# tdcs.net
KiCad netlist of a schematic drawn in EAGLE
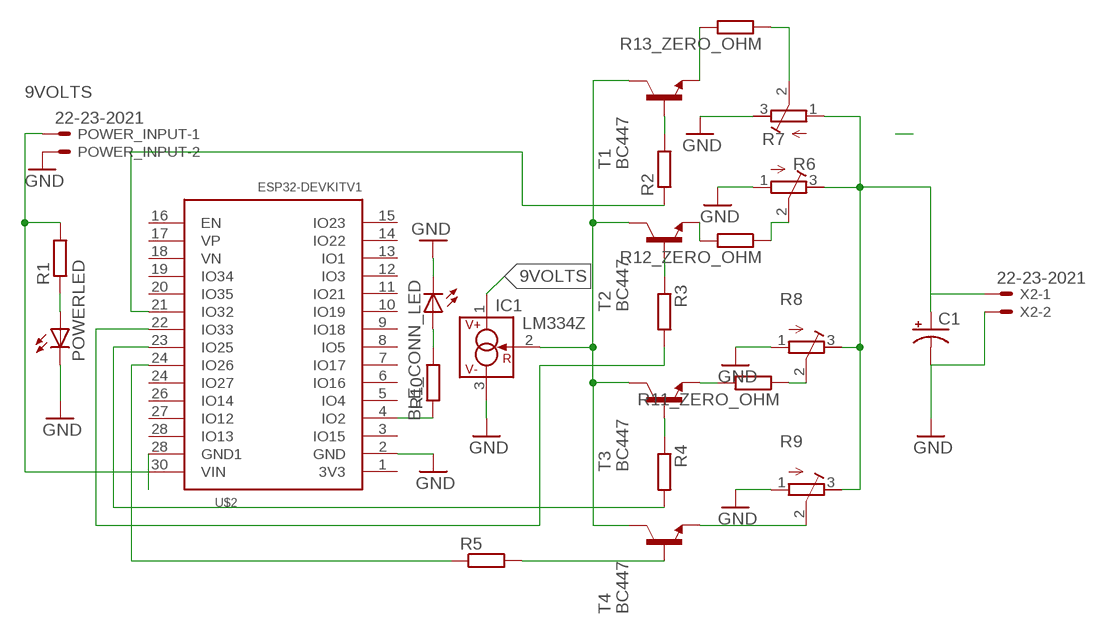
[diagram p0: schematic, sheet 1]

(export (version "E")
  (design (tool "Eeschema 10.0.6"))
  (components
    (comp (ref "BLE_CONN_LED")
      (value "LED3MM")
      (footprint "eagle-import:LED3MM")
      (libsource (lib "eagle-import") (part "LED3MM"))
    )
    (comp (ref "C1")
      (value "CPOL-USE1.8-4")
      (footprint "eagle-import:E1,8-4")
      (libsource (lib "eagle-import") (part "CPOL-USE1.8-4"))
    )
    (comp (ref "IC1")
      (value "LM334Z")
      (footprint "eagle-import:TO92")
      (libsource (lib "eagle-import") (part "LM34Z3"))
    )
    (comp (ref "POWERLED")
      (value "LEDB152")
      (footprint "eagle-import:Q62902-B152")
      (libsource (lib "eagle-import") (part "LEDB152"))
    )
    (comp (ref "POWER_INPUT")
      (value "22-23-2021")
      (footprint "eagle-import:22-23-2021")
      (fields (field (name "MF") "MOLEX"))
      (libsource (lib "eagle-import") (part "22-23-2021"))
    )
    (comp (ref "R1")
      (value "R-EU_0204/5")
      (footprint "eagle-import:0204_5")
      (libsource (lib "eagle-import") (part "R-EU_0204/5"))
    )
    (comp (ref "R2")
      (value "R-EU_0204/5")
      (footprint "eagle-import:0204_5")
      (libsource (lib "eagle-import") (part "R-EU_0204/5"))
    )
    (comp (ref "R3")
      (value "R-EU_0204/5")
      (footprint "eagle-import:0204_5")
      (libsource (lib "eagle-import") (part "R-EU_0204/5"))
    )
    (comp (ref "R4")
      (value "R-EU_0204/5")
      (footprint "eagle-import:0204_5")
      (libsource (lib "eagle-import") (part "R-EU_0204/5"))
    )
    (comp (ref "R5")
      (value "R-EU_0204/5")
      (footprint "eagle-import:0204_5")
      (libsource (lib "eagle-import") (part "R-EU_0204/5"))
    )
    (comp (ref "R6")
      (value "R-TRIMM64W")
      (footprint "eagle-import:RTRIM64W")
      (libsource (lib "eagle-import") (part "R-TRIMM64W"))
    )
    (comp (ref "R7")
      (value "R-TRIMM64W")
      (footprint "eagle-import:RTRIM64W")
      (libsource (lib "eagle-import") (part "R-TRIMM64W"))
    )
    (comp (ref "R8")
      (value "R-TRIMM64W")
      (footprint "eagle-import:RTRIM64W")
      (libsource (lib "eagle-import") (part "R-TRIMM64W"))
    )
    (comp (ref "R9")
      (value "R-TRIMM64W")
      (footprint "eagle-import:RTRIM64W")
      (libsource (lib "eagle-import") (part "R-TRIMM64W"))
    )
    (comp (ref "R10")
      (value "R-EU_0204/5")
      (footprint "eagle-import:0204_5")
      (libsource (lib "eagle-import") (part "R-EU_0204/5"))
    )
    (comp (ref "R11_ZERO_OHM")
      (value "R-EU_0204/5")
      (footprint "eagle-import:0204_5")
      (libsource (lib "eagle-import") (part "R-EU_0204/5"))
    )
    (comp (ref "R12_ZERO_OHM")
      (value "R-EU_0204/5")
      (footprint "eagle-import:0204_5")
      (libsource (lib "eagle-import") (part "R-EU_0204/5"))
    )
    (comp (ref "R13_ZERO_OHM")
      (value "R-EU_0204/5")
      (footprint "eagle-import:0204_5")
      (libsource (lib "eagle-import") (part "R-EU_0204/5"))
    )
    (comp (ref "T1")
      (value "BC447")
      (footprint "eagle-import:TO92-EBC")
      (libsource (lib "eagle-import") (part "BC447"))
    )
    (comp (ref "T2")
      (value "BC447")
      (footprint "eagle-import:TO92-EBC")
      (libsource (lib "eagle-import") (part "BC447"))
    )
    (comp (ref "T3")
      (value "BC447")
      (footprint "eagle-import:TO92-EBC")
      (libsource (lib "eagle-import") (part "BC447"))
    )
    (comp (ref "T4")
      (value "BC447")
      (footprint "eagle-import:TO92-EBC")
      (libsource (lib "eagle-import") (part "BC447"))
    )
    (comp (ref "U$2")
      (value "ESP32DEVKITV1")
      (footprint "eagle-import:ESP32-DEVKITV1")
      (libsource (lib "eagle-import") (part "ESP32DEVKITV1"))
    )
    (comp (ref "X2")
      (value "22-23-2021")
      (footprint "eagle-import:22-23-2021")
      (fields (field (name "MF") "MOLEX"))
      (libsource (lib "eagle-import") (part "22-23-2021"))
    )
  )
  (nets
    (net (code "1") (name "9VOLTS") (class "Default")
      (node (ref "IC1") (pin "1") (pinfunction "V+_1") (pintype "passive"))
      (node (ref "POWER_INPUT") (pin "1") (pinfunction "S_1") (pintype "passive"))
      (node (ref "R1") (pin "2") (pinfunction "2_2") (pintype "passive"))
      (node (ref "U$2") (pin "30") (pinfunction "VIN_30") (pintype "bidirectional"))
    )
    (net (code "2") (name "GND") (class "Default")
      (node (ref "BLE_CONN_LED") (pin "K") (pinfunction "C_K") (pintype "passive"))
      (node (ref "C1") (pin "-") (pinfunction "-_-") (pintype "passive"))
      (node (ref "IC1") (pin "3") (pinfunction "V-_3") (pintype "passive"))
      (node (ref "POWERLED") (pin "K") (pinfunction "C_K") (pintype "passive"))
      (node (ref "POWER_INPUT") (pin "2") (pinfunction "S_2") (pintype "passive"))
      (node (ref "R6") (pin "3") (pinfunction "E_3") (pintype "passive"))
      (node (ref "R7") (pin "1") (pinfunction "A_1") (pintype "passive"))
      (node (ref "R8") (pin "1") (pinfunction "A_1") (pintype "passive"))
      (node (ref "R9") (pin "1") (pinfunction "A_1") (pintype "passive"))
      (node (ref "U$2") (pin "2") (pinfunction "GND_2") (pintype "bidirectional"))
      (node (ref "X2") (pin "2") (pinfunction "S_2") (pintype "passive"))
    )
    (net (code "3") (name "Net-(BLE_CONN_LED-PadA)") (class "Default")
      (node (ref "BLE_CONN_LED") (pin "A") (pinfunction "A_A") (pintype "passive"))
      (node (ref "R10") (pin "2") (pinfunction "2_2") (pintype "passive"))
    )
    (net (code "4") (name "Net-(IC1-R)") (class "Default")
      (node (ref "IC1") (pin "2") (pinfunction "R_2") (pintype "passive"))
      (node (ref "T1") (pin "C") (pinfunction "C_C") (pintype "passive"))
      (node (ref "T2") (pin "C") (pinfunction "C_C") (pintype "passive"))
      (node (ref "T3") (pin "C") (pinfunction "C_C") (pintype "passive"))
      (node (ref "T4") (pin "C") (pinfunction "C_C") (pintype "passive"))
    )
    (net (code "5") (name "Net-(POWERLED-PadA)") (class "Default")
      (node (ref "POWERLED") (pin "A") (pinfunction "A_A") (pintype "passive"))
      (node (ref "R1") (pin "1") (pinfunction "1_1") (pintype "passive"))
    )
    (net (code "6") (name "Net-(R2-Pad2)") (class "Default")
      (node (ref "R2") (pin "2") (pinfunction "2_2") (pintype "passive"))
      (node (ref "T1") (pin "B") (pinfunction "B_B") (pintype "passive"))
    )
    (net (code "7") (name "Net-(R3-Pad1)") (class "Default")
      (node (ref "R3") (pin "1") (pinfunction "1_1") (pintype "passive"))
      (node (ref "T2") (pin "B") (pinfunction "B_B") (pintype "passive"))
    )
    (net (code "8") (name "Net-(R4-Pad1)") (class "Default")
      (node (ref "R4") (pin "1") (pinfunction "1_1") (pintype "passive"))
      (node (ref "T3") (pin "B") (pinfunction "B_B") (pintype "passive"))
    )
    (net (code "9") (name "Net-(R5-Pad2)") (class "Default")
      (node (ref "R5") (pin "2") (pinfunction "2_2") (pintype "passive"))
      (node (ref "T4") (pin "B") (pinfunction "B_B") (pintype "passive"))
    )
    (net (code "10") (name "Net-(R6-A)") (class "Default")
      (node (ref "C1") (pin "+") (pinfunction "+_+") (pintype "passive"))
      (node (ref "R6") (pin "1") (pinfunction "A_1") (pintype "passive"))
      (node (ref "R7") (pin "3") (pinfunction "E_3") (pintype "passive"))
      (node (ref "R8") (pin "3") (pinfunction "E_3") (pintype "passive"))
      (node (ref "R9") (pin "3") (pinfunction "E_3") (pintype "passive"))
      (node (ref "X2") (pin "1") (pinfunction "S_1") (pintype "passive"))
    )
    (net (code "11") (name "Net-(R6-S)") (class "Default")
      (node (ref "R13_ZERO_OHM") (pin "1") (pinfunction "1_1") (pintype "passive"))
      (node (ref "R6") (pin "2") (pinfunction "S_2") (pintype "passive"))
    )
    (net (code "12") (name "Net-(R7-S)") (class "Default")
      (node (ref "R12_ZERO_OHM") (pin "1") (pinfunction "1_1") (pintype "passive"))
      (node (ref "R7") (pin "2") (pinfunction "S_2") (pintype "passive"))
    )
    (net (code "13") (name "Net-(R8-S)") (class "Default")
      (node (ref "R11_ZERO_OHM") (pin "1") (pinfunction "1_1") (pintype "passive"))
      (node (ref "R8") (pin "2") (pinfunction "S_2") (pintype "passive"))
    )
    (net (code "14") (name "Net-(R9-S)") (class "Default")
      (node (ref "R9") (pin "2") (pinfunction "S_2") (pintype "passive"))
      (node (ref "T4") (pin "E") (pinfunction "E_E") (pintype "passive"))
    )
    (net (code "15") (name "Net-(R11_ZERO_OHM-Pad2)") (class "Default")
      (node (ref "R11_ZERO_OHM") (pin "2") (pinfunction "2_2") (pintype "passive"))
      (node (ref "T3") (pin "E") (pinfunction "E_E") (pintype "passive"))
    )
    (net (code "16") (name "Net-(R12_ZERO_OHM-Pad2)") (class "Default")
      (node (ref "R12_ZERO_OHM") (pin "2") (pinfunction "2_2") (pintype "passive"))
      (node (ref "T2") (pin "E") (pinfunction "E_E") (pintype "passive"))
    )
    (net (code "17") (name "Net-(R13_ZERO_OHM-Pad2)") (class "Default")
      (node (ref "R13_ZERO_OHM") (pin "2") (pinfunction "2_2") (pintype "passive"))
      (node (ref "T1") (pin "E") (pinfunction "E_E") (pintype "passive"))
    )
    (net (code "18") (name "Net-(U$2-IO2)") (class "Default")
      (node (ref "R10") (pin "1") (pinfunction "1_1") (pintype "passive"))
      (node (ref "U$2") (pin "4") (pinfunction "IO2_4") (pintype "bidirectional"))
    )
    (net (code "19") (name "Net-(U$2-IO25)") (class "Default")
      (node (ref "R4") (pin "2") (pinfunction "2_2") (pintype "passive"))
      (node (ref "U$2") (pin "23") (pinfunction "IO25_23") (pintype "bidirectional"))
    )
    (net (code "20") (name "Net-(U$2-IO26)") (class "Default")
      (node (ref "R5") (pin "1") (pinfunction "1_1") (pintype "passive"))
      (node (ref "U$2") (pin "24") (pinfunction "IO26_24") (pintype "bidirectional"))
    )
    (net (code "21") (name "Net-(U$2-IO32)") (class "Default")
      (node (ref "R2") (pin "1") (pinfunction "1_1") (pintype "passive"))
      (node (ref "U$2") (pin "21") (pinfunction "IO32_21") (pintype "bidirectional"))
    )
    (net (code "22") (name "Net-(U$2-IO33)") (class "Default")
      (node (ref "R3") (pin "2") (pinfunction "2_2") (pintype "passive"))
      (node (ref "U$2") (pin "22") (pinfunction "IO33_22") (pintype "bidirectional"))
    )
    (net (code "23") (name "unconnected-(U$2-3V3-Pad1)") (class "Default")
      (node (ref "U$2") (pin "1") (pinfunction "3V3_1") (pintype "bidirectional"))
    )
    (net (code "24") (name "unconnected-(U$2-EN-Pad16)") (class "Default")
      (node (ref "U$2") (pin "16") (pinfunction "EN_16") (pintype "bidirectional"))
    )
    (net (code "25") (name "unconnected-(U$2-GND1-Pad28)") (class "Default")
      (node (ref "U$2") (pin "28") (pinfunction "GND1_28") (pintype "bidirectional"))
    )
    (net (code "26") (name "unconnected-(U$2-IO1-Pad13)") (class "Default")
      (node (ref "U$2") (pin "13") (pinfunction "IO1_13") (pintype "bidirectional"))
    )
    (net (code "27") (name "unconnected-(U$2-IO3-Pad12)") (class "Default")
      (node (ref "U$2") (pin "12") (pinfunction "IO3_12") (pintype "bidirectional"))
    )
    (net (code "28") (name "unconnected-(U$2-IO4-Pad5)") (class "Default")
      (node (ref "U$2") (pin "5") (pinfunction "IO4_5") (pintype "bidirectional"))
    )
    (net (code "29") (name "unconnected-(U$2-IO5-Pad8)") (class "Default")
      (node (ref "U$2") (pin "8") (pinfunction "IO5_8") (pintype "bidirectional"))
    )
    (net (code "30") (name "unconnected-(U$2-IO12-Pad27)") (class "Default")
      (node (ref "U$2") (pin "27") (pinfunction "IO12_27") (pintype "bidirectional"))
    )
    (net (code "31") (name "unconnected-(U$2-IO13-Pad28)") (class "Default")
      (node (ref "U$2") (pin "28") (pinfunction "IO13_28") (pintype "bidirectional"))
    )
    (net (code "32") (name "unconnected-(U$2-IO14-Pad26)") (class "Default")
      (node (ref "U$2") (pin "26") (pinfunction "IO14_26") (pintype "bidirectional"))
    )
    (net (code "33") (name "unconnected-(U$2-IO15-Pad3)") (class "Default")
      (node (ref "U$2") (pin "3") (pinfunction "IO15_3") (pintype "bidirectional"))
    )
    (net (code "34") (name "unconnected-(U$2-IO16-Pad6)") (class "Default")
      (node (ref "U$2") (pin "6") (pinfunction "IO16_6") (pintype "bidirectional"))
    )
    (net (code "35") (name "unconnected-(U$2-IO17-Pad7)") (class "Default")
      (node (ref "U$2") (pin "7") (pinfunction "IO17_7") (pintype "bidirectional"))
    )
    (net (code "36") (name "unconnected-(U$2-IO18-Pad9)") (class "Default")
      (node (ref "U$2") (pin "9") (pinfunction "IO18_9") (pintype "bidirectional"))
    )
    (net (code "37") (name "unconnected-(U$2-IO19-Pad10)") (class "Default")
      (node (ref "U$2") (pin "10") (pinfunction "IO19_10") (pintype "bidirectional"))
    )
    (net (code "38") (name "unconnected-(U$2-IO21-Pad11)") (class "Default")
      (node (ref "U$2") (pin "11") (pinfunction "IO21_11") (pintype "bidirectional"))
    )
    (net (code "39") (name "unconnected-(U$2-IO22-Pad14)") (class "Default")
      (node (ref "U$2") (pin "14") (pinfunction "IO22_14") (pintype "bidirectional"))
    )
    (net (code "40") (name "unconnected-(U$2-IO23-Pad15)") (class "Default")
      (node (ref "U$2") (pin "15") (pinfunction "IO23_15") (pintype "bidirectional"))
    )
    (net (code "41") (name "unconnected-(U$2-IO27-Pad24)") (class "Default")
      (node (ref "U$2") (pin "24") (pinfunction "IO27_24") (pintype "bidirectional"))
    )
    (net (code "42") (name "unconnected-(U$2-IO34-Pad19)") (class "Default")
      (node (ref "U$2") (pin "19") (pinfunction "IO34_19") (pintype "bidirectional"))
    )
    (net (code "43") (name "unconnected-(U$2-IO35-Pad20)") (class "Default")
      (node (ref "U$2") (pin "20") (pinfunction "IO35_20") (pintype "bidirectional"))
    )
    (net (code "44") (name "unconnected-(U$2-VN-Pad18)") (class "Default")
      (node (ref "U$2") (pin "18") (pinfunction "VN_18") (pintype "bidirectional"))
    )
    (net (code "45") (name "unconnected-(U$2-VP-Pad17)") (class "Default")
      (node (ref "U$2") (pin "17") (pinfunction "VP_17") (pintype "bidirectional"))
    )
  )
)
